# RHD2132_lvds_headstage_3_1_smaller_01.net
KiCad netlist of a schematic drawn in EAGLE
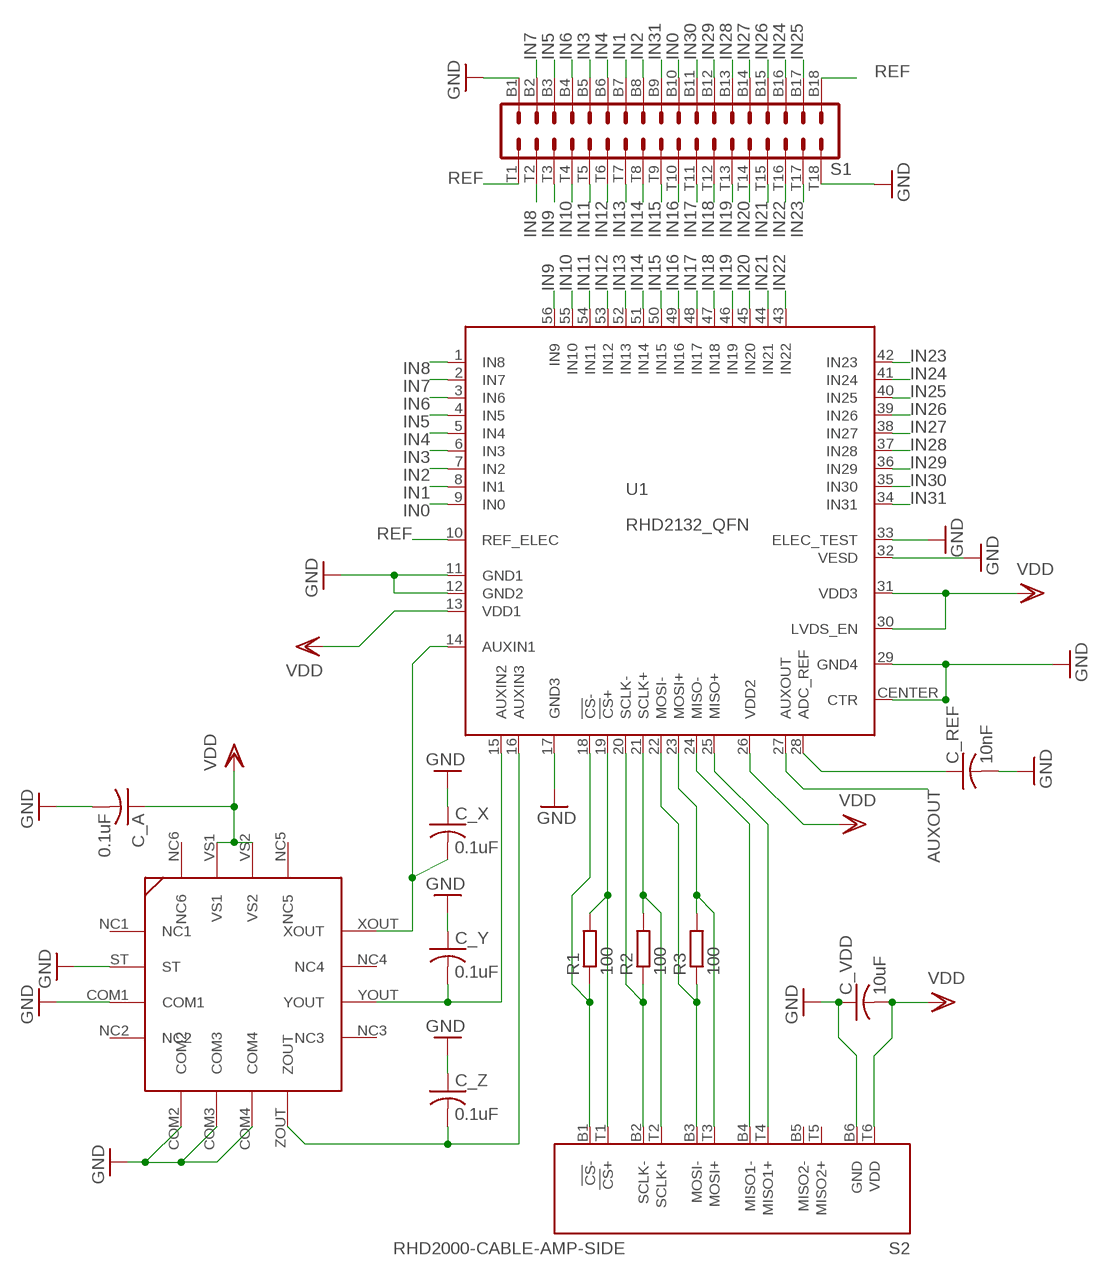
[diagram p0: schematic, sheet 1]

(export (version "E")
  (design (tool "Eeschema 10.0.6"))
  (components
    (comp (ref "C_A")
      (value "0.1uF")
      (footprint "eagle-import:C0402K")
      (libsource (lib "eagle-import") (part "C-USC0402K"))
    )
    (comp (ref "C_REF")
      (value "10nF")
      (footprint "eagle-import:C0402K")
      (libsource (lib "eagle-import") (part "C-USC0402K"))
    )
    (comp (ref "C_VDD")
      (value "10uF")
      (footprint "eagle-import:C0402K")
      (libsource (lib "eagle-import") (part "C-USC0402K"))
    )
    (comp (ref "C_X")
      (value "0.1uF")
      (footprint "eagle-import:C0402K")
      (libsource (lib "eagle-import") (part "C-USC0402K"))
    )
    (comp (ref "C_Y")
      (value "0.1uF")
      (footprint "eagle-import:C0402K")
      (libsource (lib "eagle-import") (part "C-USC0402K"))
    )
    (comp (ref "C_Z")
      (value "0.1uF")
      (footprint "eagle-import:C0402K")
      (libsource (lib "eagle-import") (part "C-USC0402K"))
    )
    (comp (ref "R1")
      (value "100")
      (footprint "eagle-import:R0402")
      (libsource (lib "eagle-import") (part "R-EU_R0402"))
    )
    (comp (ref "R2")
      (value "100")
      (footprint "eagle-import:R0402")
      (libsource (lib "eagle-import") (part "R-EU_R0402"))
    )
    (comp (ref "R3")
      (value "100")
      (footprint "eagle-import:R0402")
      (libsource (lib "eagle-import") (part "R-EU_R0402"))
    )
    (comp (ref "S1")
      (value "OMNETICS_A79025")
      (footprint "eagle-import:OMNETICS_A79025")
      (libsource (lib "eagle-import") (part "OMNETICS_A79025"))
    )
    (comp (ref "S2")
      (value "RHD2000-CABLE-AMP-SIDE")
      (footprint "eagle-import:OMNETICS_PZN-12-AA")
      (libsource (lib "eagle-import") (part "RHD2000-CABLE-AMP-SIDE"))
    )
    (comp (ref "U$1")
      (value "ADXL335")
      (footprint "eagle-import:ADXL335")
      (libsource (lib "eagle-import") (part "ADXL335"))
    )
    (comp (ref "U1")
      (value "RHD2132_QFN")
      (footprint "eagle-import:QFN56_8_X_8_LARGE")
      (libsource (lib "eagle-import") (part "RHD2132_QFN"))
    )
  )
  (nets
    (net (code "1") (name "/AUXOUT") (class "Default")
      (node (ref "U1") (pin "27") (pinfunction "AUXOUT_27") (pintype "tri_state"))
    )
    (net (code "2") (name "/IN0") (class "Default")
      (node (ref "S1") (pin "B10") (pinfunction "B10_B10") (pintype "passive"))
      (node (ref "U1") (pin "9") (pinfunction "IN0_9") (pintype "input"))
    )
    (net (code "3") (name "/IN1") (class "Default")
      (node (ref "S1") (pin "B7") (pinfunction "B7_B7") (pintype "passive"))
      (node (ref "U1") (pin "8") (pinfunction "IN1_8") (pintype "input"))
    )
    (net (code "4") (name "/IN2") (class "Default")
      (node (ref "S1") (pin "B8") (pinfunction "B8_B8") (pintype "passive"))
      (node (ref "U1") (pin "7") (pinfunction "IN2_7") (pintype "input"))
    )
    (net (code "5") (name "/IN3") (class "Default")
      (node (ref "S1") (pin "B5") (pinfunction "B5_B5") (pintype "passive"))
      (node (ref "U1") (pin "6") (pinfunction "IN3_6") (pintype "input"))
    )
    (net (code "6") (name "/IN4") (class "Default")
      (node (ref "S1") (pin "B6") (pinfunction "B6_B6") (pintype "passive"))
      (node (ref "U1") (pin "5") (pinfunction "IN4_5") (pintype "input"))
    )
    (net (code "7") (name "/IN5") (class "Default")
      (node (ref "S1") (pin "B3") (pinfunction "B3_B3") (pintype "passive"))
      (node (ref "U1") (pin "4") (pinfunction "IN5_4") (pintype "input"))
    )
    (net (code "8") (name "/IN6") (class "Default")
      (node (ref "S1") (pin "B4") (pinfunction "B4_B4") (pintype "passive"))
      (node (ref "U1") (pin "3") (pinfunction "IN6_3") (pintype "input"))
    )
    (net (code "9") (name "/IN7") (class "Default")
      (node (ref "S1") (pin "B2") (pinfunction "B2_B2") (pintype "passive"))
      (node (ref "U1") (pin "2") (pinfunction "IN7_2") (pintype "input"))
    )
    (net (code "10") (name "/IN8") (class "Default")
      (node (ref "S1") (pin "T2") (pinfunction "T2_T2") (pintype "passive"))
      (node (ref "U1") (pin "1") (pinfunction "IN8_1") (pintype "input"))
    )
    (net (code "11") (name "/IN9") (class "Default")
      (node (ref "S1") (pin "T3") (pinfunction "T3_T3") (pintype "passive"))
      (node (ref "U1") (pin "56") (pinfunction "IN9_56") (pintype "input"))
    )
    (net (code "12") (name "/IN10") (class "Default")
      (node (ref "S1") (pin "T4") (pinfunction "T4_T4") (pintype "passive"))
      (node (ref "U1") (pin "55") (pinfunction "IN10_55") (pintype "input"))
    )
    (net (code "13") (name "/IN11") (class "Default")
      (node (ref "S1") (pin "T5") (pinfunction "T5_T5") (pintype "passive"))
      (node (ref "U1") (pin "54") (pinfunction "IN11_54") (pintype "input"))
    )
    (net (code "14") (name "/IN12") (class "Default")
      (node (ref "S1") (pin "T6") (pinfunction "T6_T6") (pintype "passive"))
      (node (ref "U1") (pin "53") (pinfunction "IN12_53") (pintype "input"))
    )
    (net (code "15") (name "/IN13") (class "Default")
      (node (ref "S1") (pin "T7") (pinfunction "T7_T7") (pintype "passive"))
      (node (ref "U1") (pin "52") (pinfunction "IN13_52") (pintype "input"))
    )
    (net (code "16") (name "/IN14") (class "Default")
      (node (ref "S1") (pin "T8") (pinfunction "T8_T8") (pintype "passive"))
      (node (ref "U1") (pin "51") (pinfunction "IN14_51") (pintype "input"))
    )
    (net (code "17") (name "/IN15") (class "Default")
      (node (ref "S1") (pin "T9") (pinfunction "T9_T9") (pintype "passive"))
      (node (ref "U1") (pin "50") (pinfunction "IN15_50") (pintype "input"))
    )
    (net (code "18") (name "/IN16") (class "Default")
      (node (ref "S1") (pin "T10") (pinfunction "T10_T10") (pintype "passive"))
      (node (ref "U1") (pin "49") (pinfunction "IN16_49") (pintype "input"))
    )
    (net (code "19") (name "/IN17") (class "Default")
      (node (ref "S1") (pin "T11") (pinfunction "T11_T11") (pintype "passive"))
      (node (ref "U1") (pin "48") (pinfunction "IN17_48") (pintype "input"))
    )
    (net (code "20") (name "/IN18") (class "Default")
      (node (ref "S1") (pin "T12") (pinfunction "T12_T12") (pintype "passive"))
      (node (ref "U1") (pin "47") (pinfunction "IN18_47") (pintype "input"))
    )
    (net (code "21") (name "/IN19") (class "Default")
      (node (ref "S1") (pin "T13") (pinfunction "T13_T13") (pintype "passive"))
      (node (ref "U1") (pin "46") (pinfunction "IN19_46") (pintype "input"))
    )
    (net (code "22") (name "/IN20") (class "Default")
      (node (ref "S1") (pin "T14") (pinfunction "T14_T14") (pintype "passive"))
      (node (ref "U1") (pin "45") (pinfunction "IN20_45") (pintype "input"))
    )
    (net (code "23") (name "/IN21") (class "Default")
      (node (ref "S1") (pin "T15") (pinfunction "T15_T15") (pintype "passive"))
      (node (ref "U1") (pin "44") (pinfunction "IN21_44") (pintype "input"))
    )
    (net (code "24") (name "/IN22") (class "Default")
      (node (ref "S1") (pin "T16") (pinfunction "T16_T16") (pintype "passive"))
      (node (ref "U1") (pin "43") (pinfunction "IN22_43") (pintype "input"))
    )
    (net (code "25") (name "/IN23") (class "Default")
      (node (ref "S1") (pin "T17") (pinfunction "T17_T17") (pintype "passive"))
      (node (ref "U1") (pin "42") (pinfunction "IN23_42") (pintype "input"))
    )
    (net (code "26") (name "/IN24") (class "Default")
      (node (ref "S1") (pin "B16") (pinfunction "B16_B16") (pintype "passive"))
      (node (ref "U1") (pin "41") (pinfunction "IN24_41") (pintype "input"))
    )
    (net (code "27") (name "/IN25") (class "Default")
      (node (ref "S1") (pin "B17") (pinfunction "B17_B17") (pintype "passive"))
      (node (ref "U1") (pin "40") (pinfunction "IN25_40") (pintype "input"))
    )
    (net (code "28") (name "/IN26") (class "Default")
      (node (ref "S1") (pin "B15") (pinfunction "B15_B15") (pintype "passive"))
      (node (ref "U1") (pin "39") (pinfunction "IN26_39") (pintype "input"))
    )
    (net (code "29") (name "/IN27") (class "Default")
      (node (ref "S1") (pin "B14") (pinfunction "B14_B14") (pintype "passive"))
      (node (ref "U1") (pin "38") (pinfunction "IN27_38") (pintype "input"))
    )
    (net (code "30") (name "/IN28") (class "Default")
      (node (ref "S1") (pin "B13") (pinfunction "B13_B13") (pintype "passive"))
      (node (ref "U1") (pin "37") (pinfunction "IN28_37") (pintype "input"))
    )
    (net (code "31") (name "/IN29") (class "Default")
      (node (ref "S1") (pin "B12") (pinfunction "B12_B12") (pintype "passive"))
      (node (ref "U1") (pin "36") (pinfunction "IN29_36") (pintype "input"))
    )
    (net (code "32") (name "/IN30") (class "Default")
      (node (ref "S1") (pin "B11") (pinfunction "B11_B11") (pintype "passive"))
      (node (ref "U1") (pin "35") (pinfunction "IN30_35") (pintype "input"))
    )
    (net (code "33") (name "/IN31") (class "Default")
      (node (ref "S1") (pin "B9") (pinfunction "B9_B9") (pintype "passive"))
      (node (ref "U1") (pin "34") (pinfunction "IN31_34") (pintype "input"))
    )
    (net (code "34") (name "/REF") (class "Default")
      (node (ref "S1") (pin "B18") (pinfunction "B18_B18") (pintype "passive"))
      (node (ref "S1") (pin "T1") (pinfunction "T1_T1") (pintype "passive"))
      (node (ref "U1") (pin "10") (pinfunction "REF_ELEC_10") (pintype "input"))
    )
    (net (code "35") (name "GND") (class "Default")
      (node (ref "C_A") (pin "2") (pinfunction "2_2") (pintype "passive"))
      (node (ref "C_REF") (pin "2") (pinfunction "2_2") (pintype "passive"))
      (node (ref "C_VDD") (pin "1") (pinfunction "1_1") (pintype "passive"))
      (node (ref "C_X") (pin "1") (pinfunction "1_1") (pintype "passive"))
      (node (ref "C_Y") (pin "1") (pinfunction "1_1") (pintype "passive"))
      (node (ref "C_Z") (pin "1") (pinfunction "1_1") (pintype "passive"))
      (node (ref "S1") (pin "B1") (pinfunction "B1_B1") (pintype "passive"))
      (node (ref "S1") (pin "T18") (pinfunction "T18_T18") (pintype "passive"))
      (node (ref "S2") (pin "B6") (pinfunction "GND_B6") (pintype "power_in"))
      (node (ref "U$1") (pin "COM1") (pinfunction "COM1_COM1") (pintype "bidirectional"))
      (node (ref "U$1") (pin "COM2") (pinfunction "COM2_COM2") (pintype "bidirectional"))
      (node (ref "U$1") (pin "COM3") (pinfunction "COM3_COM3") (pintype "bidirectional"))
      (node (ref "U$1") (pin "COM4") (pinfunction "COM4_COM4") (pintype "bidirectional"))
      (node (ref "U$1") (pin "ST") (pinfunction "ST_ST") (pintype "bidirectional"))
      (node (ref "U1") (pin "11") (pinfunction "GND1_11") (pintype "power_in"))
      (node (ref "U1") (pin "12") (pinfunction "GND2_12") (pintype "power_in"))
      (node (ref "U1") (pin "17") (pinfunction "GND3_17") (pintype "power_in"))
      (node (ref "U1") (pin "29") (pinfunction "GND4_29") (pintype "power_in"))
      (node (ref "U1") (pin "32") (pinfunction "VESD_32") (pintype "power_in"))
      (node (ref "U1") (pin "33") (pinfunction "ELEC_TEST_33") (pintype "input"))
      (node (ref "U1") (pin "CENTER") (pinfunction "CTR_CENTER") (pintype "power_in"))
    )
    (net (code "36") (name "Net-(S2-MISO1+)") (class "Default")
      (node (ref "S2") (pin "T4") (pinfunction "MISO1+_T4") (pintype "bidirectional"))
      (node (ref "U1") (pin "25") (pinfunction "MISO+_25") (pintype "output"))
    )
    (net (code "37") (name "Net-(S2-MISO1-)") (class "Default")
      (node (ref "S2") (pin "B4") (pinfunction "MISO1-_B4") (pintype "bidirectional"))
      (node (ref "U1") (pin "24") (pinfunction "MISO-_24") (pintype "output"))
    )
    (net (code "38") (name "Net-(S2-MOSI+)") (class "Default")
      (node (ref "R3") (pin "2") (pinfunction "2_2") (pintype "passive"))
      (node (ref "S2") (pin "T3") (pinfunction "MOSI+_T3") (pintype "bidirectional"))
      (node (ref "U1") (pin "23") (pinfunction "MOSI+_23") (pintype "input"))
    )
    (net (code "39") (name "Net-(S2-MOSI-)") (class "Default")
      (node (ref "R3") (pin "1") (pinfunction "1_1") (pintype "passive"))
      (node (ref "S2") (pin "B3") (pinfunction "MOSI-_B3") (pintype "bidirectional"))
      (node (ref "U1") (pin "22") (pinfunction "MOSI-_22") (pintype "input"))
    )
    (net (code "40") (name "Net-(S2-SCLK+)") (class "Default")
      (node (ref "R2") (pin "2") (pinfunction "2_2") (pintype "passive"))
      (node (ref "S2") (pin "T2") (pinfunction "SCLK+_T2") (pintype "bidirectional"))
      (node (ref "U1") (pin "21") (pinfunction "SCLK+_21") (pintype "input"))
    )
    (net (code "41") (name "Net-(S2-SCLK-)") (class "Default")
      (node (ref "R2") (pin "1") (pinfunction "1_1") (pintype "passive"))
      (node (ref "S2") (pin "B2") (pinfunction "SCLK-_B2") (pintype "bidirectional"))
      (node (ref "U1") (pin "20") (pinfunction "SCLK-_20") (pintype "input"))
    )
    (net (code "42") (name "Net-(S2-~{CS}+)") (class "Default")
      (node (ref "R1") (pin "2") (pinfunction "2_2") (pintype "passive"))
      (node (ref "S2") (pin "T1") (pinfunction "~{CS}+_T1") (pintype "bidirectional"))
      (node (ref "U1") (pin "19") (pinfunction "~{CS}+_19") (pintype "input"))
    )
    (net (code "43") (name "Net-(S2-~{CS}-)") (class "Default")
      (node (ref "R1") (pin "1") (pinfunction "1_1") (pintype "passive"))
      (node (ref "S2") (pin "B1") (pinfunction "~{CS}-_B1") (pintype "bidirectional"))
      (node (ref "U1") (pin "18") (pinfunction "~{CS}-_18") (pintype "input"))
    )
    (net (code "44") (name "Net-(U1-ADC_REF)") (class "Default")
      (node (ref "C_REF") (pin "1") (pinfunction "1_1") (pintype "passive"))
      (node (ref "U1") (pin "28") (pinfunction "ADC_REF_28") (pintype "passive"))
    )
    (net (code "45") (name "Net-(U1-AUXIN1)") (class "Default")
      (node (ref "C_X") (pin "2") (pinfunction "2_2") (pintype "passive"))
      (node (ref "U$1") (pin "XOUT") (pinfunction "XOUT_XOUT") (pintype "bidirectional"))
      (node (ref "U1") (pin "14") (pinfunction "AUXIN1_14") (pintype "input"))
    )
    (net (code "46") (name "Net-(U1-AUXIN2)") (class "Default")
      (node (ref "C_Y") (pin "2") (pinfunction "2_2") (pintype "passive"))
      (node (ref "U$1") (pin "YOUT") (pinfunction "YOUT_YOUT") (pintype "bidirectional"))
      (node (ref "U1") (pin "15") (pinfunction "AUXIN2_15") (pintype "input"))
    )
    (net (code "47") (name "Net-(U1-AUXIN3)") (class "Default")
      (node (ref "C_Z") (pin "2") (pinfunction "2_2") (pintype "passive"))
      (node (ref "U$1") (pin "ZOUT") (pinfunction "ZOUT_ZOUT") (pintype "bidirectional"))
      (node (ref "U1") (pin "16") (pinfunction "AUXIN3_16") (pintype "input"))
    )
    (net (code "48") (name "VDD") (class "Default")
      (node (ref "C_A") (pin "1") (pinfunction "1_1") (pintype "passive"))
      (node (ref "C_VDD") (pin "2") (pinfunction "2_2") (pintype "passive"))
      (node (ref "S2") (pin "T6") (pinfunction "VDD_T6") (pintype "bidirectional"))
      (node (ref "U$1") (pin "VS1") (pinfunction "VS1_VS1") (pintype "bidirectional"))
      (node (ref "U$1") (pin "VS2") (pinfunction "VS2_VS2") (pintype "bidirectional"))
      (node (ref "U1") (pin "13") (pinfunction "VDD1_13") (pintype "power_in"))
      (node (ref "U1") (pin "26") (pinfunction "VDD2_26") (pintype "power_in"))
      (node (ref "U1") (pin "30") (pinfunction "LVDS_EN_30") (pintype "input"))
      (node (ref "U1") (pin "31") (pinfunction "VDD3_31") (pintype "power_in"))
    )
    (net (code "49") (name "unconnected-(S2-MISO2+-PadT5)") (class "Default")
      (node (ref "S2") (pin "T5") (pinfunction "MISO2+_T5") (pintype "bidirectional"))
    )
    (net (code "50") (name "unconnected-(S2-MISO2--PadB5)") (class "Default")
      (node (ref "S2") (pin "B5") (pinfunction "MISO2-_B5") (pintype "bidirectional"))
    )
    (net (code "51") (name "unconnected-(U$1-PadNC1)") (class "Default")
      (node (ref "U$1") (pin "NC1") (pinfunction "NC1_NC1") (pintype "bidirectional"))
    )
    (net (code "52") (name "unconnected-(U$1-PadNC2)") (class "Default")
      (node (ref "U$1") (pin "NC2") (pinfunction "NC2_NC2") (pintype "bidirectional"))
    )
    (net (code "53") (name "unconnected-(U$1-PadNC3)") (class "Default")
      (node (ref "U$1") (pin "NC3") (pinfunction "NC3_NC3") (pintype "bidirectional"))
    )
    (net (code "54") (name "unconnected-(U$1-PadNC4)") (class "Default")
      (node (ref "U$1") (pin "NC4") (pinfunction "NC4_NC4") (pintype "bidirectional"))
    )
    (net (code "55") (name "unconnected-(U$1-PadNC5)") (class "Default")
      (node (ref "U$1") (pin "NC5") (pinfunction "NC5_NC5") (pintype "bidirectional"))
    )
    (net (code "56") (name "unconnected-(U$1-PadNC6)") (class "Default")
      (node (ref "U$1") (pin "NC6") (pinfunction "NC6_NC6") (pintype "bidirectional"))
    )
  )
)
